# MCU.net
KiCad netlist of a schematic drawn in Altium Designer
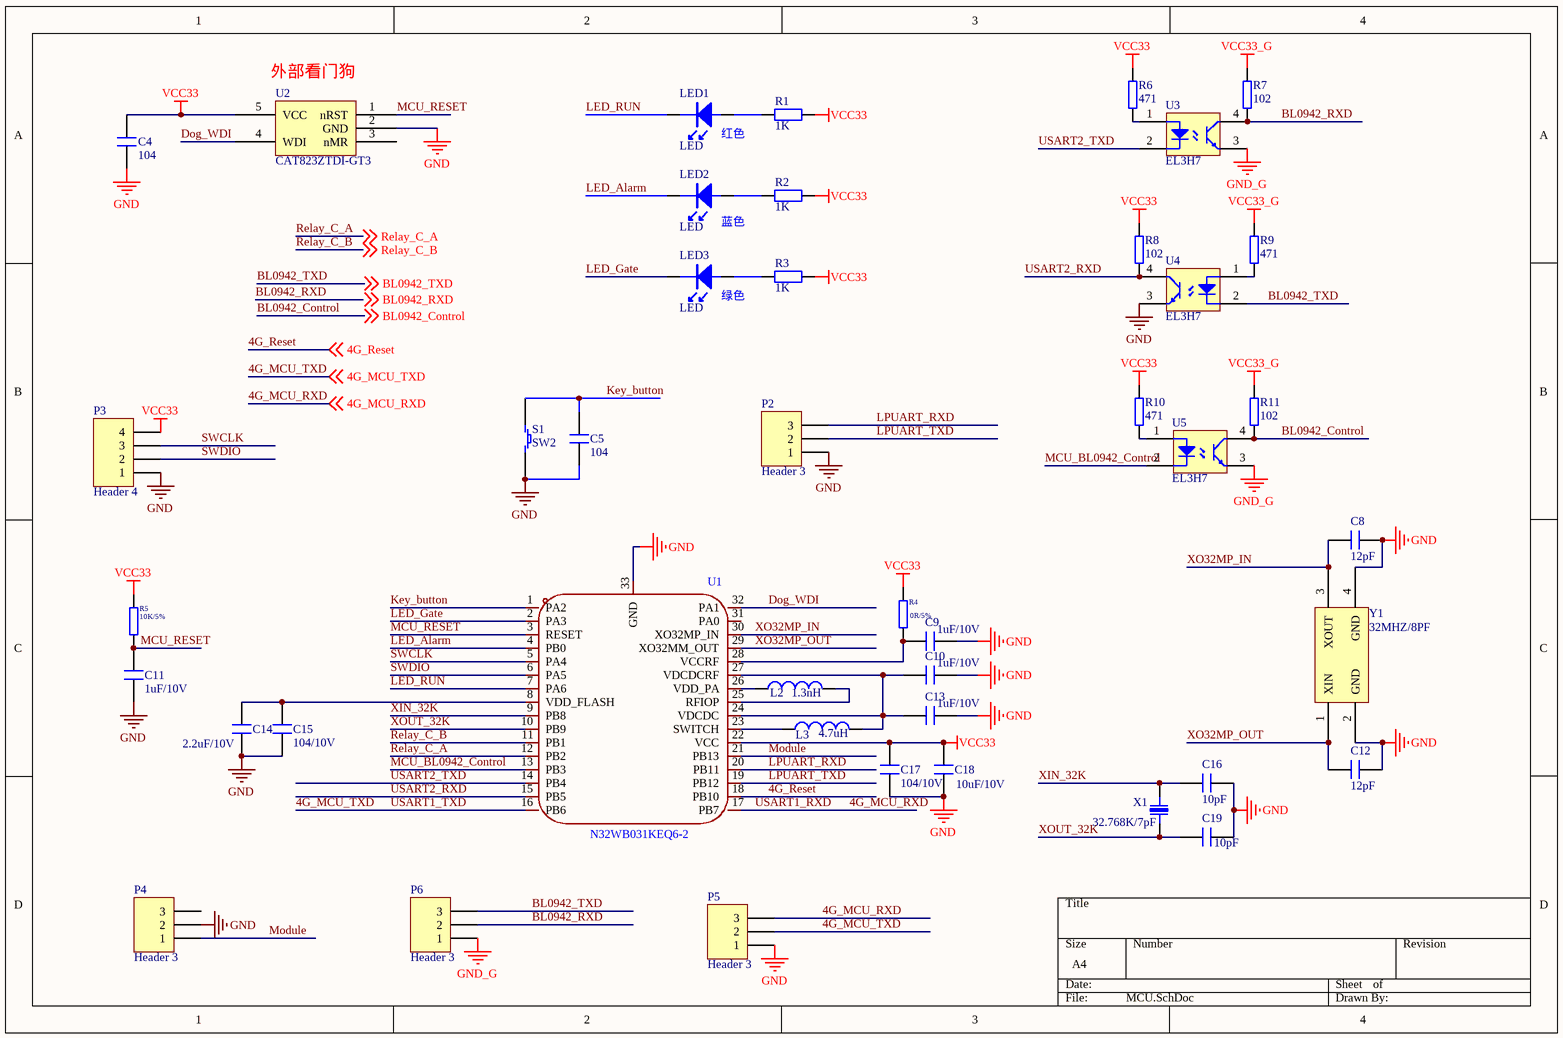
[diagram p0: MCU.SchDoc]

(export (version "E")
  (design (tool "Eeschema 10.0.6"))
  (components
    (comp (ref "C4") (value "104") (footprint "0603R") (libsource (lib "ES_Schematic") (part "CAP")))
    (comp (ref "C5") (value "104") (footprint "0603R") (libsource (lib "ES_Schematic") (part "CAP")))
    (comp (ref "C8") (value "12pF") (footprint "0603r") (libsource (lib "ES_Schematic") (part "CAP")))
    (comp (ref "C9") (value "1uF/10V") (footprint "0603R") (libsource (lib "ES_Schematic") (part "CAP_1")))
    (comp (ref "C10") (value "1uF/10V") (footprint "0603R") (libsource (lib "ES_Schematic") (part "CAP_1")))
    (comp (ref "C11") (value "1uF/10V") (footprint "0603R") (libsource (lib "ES_Schematic") (part "CAP_1")))
    (comp (ref "C12") (value "12pF") (footprint "0603r") (libsource (lib "ES_Schematic") (part "CAP")))
    (comp (ref "C13") (value "1uF/10V") (footprint "0603R") (libsource (lib "ES_Schematic") (part "CAP_1")))
    (comp (ref "C14") (value "2.2uF/10V") (footprint "0603R") (libsource (lib "ES_Schematic") (part "CAP_1")))
    (comp (ref "C15") (value "104/10V") (footprint "0603R") (libsource (lib "ES_Schematic") (part "CAP_1")))
    (comp (ref "C16") (value "10pF") (footprint "0603r") (libsource (lib "ES_Schematic") (part "CAP")))
    (comp (ref "C17") (value "104/10V") (footprint "0603R") (libsource (lib "ES_Schematic") (part "CAP_1")))
    (comp (ref "C18") (value "10uF/10V") (footprint "0603R") (libsource (lib "ES_Schematic") (part "CAP_1")))
    (comp (ref "C19") (value "10pF") (footprint "0603r") (libsource (lib "ES_Schematic") (part "CAP")))
    (comp (ref "L2")
      (value "1.3nH")
      (footprint "0603R")
      (description "Inductor")
      (fields (field (name "PUBLISHER") "Altium Limited"))
      (libsource (lib "Miscellaneous Devices") (part "Inductor"))
    )
    (comp (ref "L3")
      (value "4.7uH")
      (footprint "0603R")
      (description "Inductor")
      (fields (field (name "PUBLISHER") "Altium Limited"))
      (libsource (lib "Miscellaneous Devices") (part "Inductor"))
    )
    (comp (ref "LED1") (value "LED") (footprint "LED0805") (libsource (lib "ES_Schematic") (part "LED")))
    (comp (ref "LED2") (value "LED") (footprint "LED0805") (libsource (lib "ES_Schematic") (part "LED")))
    (comp (ref "LED3") (value "LED") (footprint "LED0805") (libsource (lib "ES_Schematic") (part "LED")))
    (comp (ref "P2")
      (value "Header 3")
      (footprint "HDR1X3")
      (description "Header, 3-Pin")
      (fields (field (name "PUBLISHER") "Altium Limited"))
      (libsource (lib "Miscellaneous Connectors") (part "Header 3"))
    )
    (comp (ref "P3")
      (value "Header 4")
      (footprint "HDR1X4")
      (description "Header, 4-Pin")
      (fields (field (name "PUBLISHER") "Altium Limited"))
      (libsource (lib "Miscellaneous Connectors") (part "Header 4"))
    )
    (comp (ref "P4")
      (value "Header 3")
      (footprint "Ss-12D00")
      (description "Header, 3-Pin")
      (fields (field (name "PUBLISHER") "Altium Limited"))
      (libsource (lib "Miscellaneous Connectors") (part "Header 3"))
    )
    (comp (ref "P5")
      (value "Header 3")
      (footprint "HDR1X3")
      (description "Header, 3-Pin")
      (fields (field (name "PUBLISHER") "Altium Limited"))
      (libsource (lib "Miscellaneous Connectors") (part "Header 3"))
    )
    (comp (ref "P6")
      (value "Header 3")
      (footprint "HDR1X3")
      (description "Header, 3-Pin")
      (fields (field (name "PUBLISHER") "Altium Limited"))
      (libsource (lib "Miscellaneous Connectors") (part "Header 3"))
    )
    (comp (ref "R1")
      (value "1K")
      (footprint "0603R")
      (fields (field (name "Comment") "Res2") (field (name "PUBLISHER") "Altium Limited"))
      (libsource (lib "Miscellaneous Devices") (part "Res2"))
    )
    (comp (ref "R2")
      (value "1K")
      (footprint "0603R")
      (fields (field (name "Comment") "Res2") (field (name "PUBLISHER") "Altium Limited"))
      (libsource (lib "Miscellaneous Devices") (part "Res2"))
    )
    (comp (ref "R3")
      (value "1K")
      (footprint "0603R")
      (fields (field (name "Comment") "Res2") (field (name "PUBLISHER") "Altium Limited"))
      (libsource (lib "Miscellaneous Devices") (part "Res2"))
    )
    (comp (ref "R4") (value "0R/5%") (footprint "0603R") (libsource (lib "ES_Schematic") (part "RES")))
    (comp (ref "R5") (value "10K/5%") (footprint "0603R") (libsource (lib "ES_Schematic") (part "RES")))
    (comp (ref "R6") (value "471") (footprint "0603R") (libsource (lib "ES_Schematic") (part "RES")))
    (comp (ref "R7") (value "102") (footprint "0603R") (libsource (lib "ES_Schematic") (part "RES")))
    (comp (ref "R8") (value "102") (footprint "0603R") (libsource (lib "ES_Schematic") (part "RES")))
    (comp (ref "R9") (value "471") (footprint "0603R") (libsource (lib "ES_Schematic") (part "RES")))
    (comp (ref "R10") (value "471") (footprint "0603R") (libsource (lib "ES_Schematic") (part "RES")))
    (comp (ref "R11") (value "102") (footprint "0603R") (libsource (lib "ES_Schematic") (part "RES")))
    (comp (ref "S1")
      (value "SW2")
      (footprint "4.5*4.5贴片4脚独立按键")
      (libsource (lib "ES_Schematic") (part "SW2"))
    )
    (comp (ref "U1")
      (value "N32WB031KEQ6-2")
      (footprint "QFN-32_L4.0-W4.0-P0.40-TL-EP2.8")
      (fields (field (name "MANUFACTURER") "Nations(国民技术)"))
      (libsource (lib "altium-import") (part "root_0_N32WB031KEQ6-2_"))
    )
    (comp (ref "U2")
      (value "CAT823ZTDI-GT3")
      (footprint "SOT-23-5")
      (libsource (lib "ES_Schematic") (part "CAT823"))
    )
    (comp (ref "U3") (value "EL3H7") (footprint "EL3H7") (libsource (lib "") (part "Optical_Coupler_1_1")))
    (comp (ref "U4")
      (value "EL3H7")
      (footprint "EL3H7")
      (libsource (lib "ES_Schematic") (part "Optical_Coupler_1"))
    )
    (comp (ref "U5") (value "EL3H7") (footprint "EL3H7") (libsource (lib "") (part "Optical_Coupler_1_1")))
    (comp (ref "X1") (value "32.768K/7pF") (footprint "Y3215") (libsource (lib "ES_Schematic") (part "XTAL")))
    (comp (ref "Y1") (value "32MHZ/8PF") (footprint "3225") (libsource (lib "others") (part "12MHz无源")))
  )
  (nets
    (net (code "1") (name "/Dog_WDI") (class "Default")
      (node (ref "U1") (pin "32") (pinfunction "PA1_32") (pintype "passive"))
      (node (ref "U2") (pin "4") (pinfunction "WDI_4") (pintype "passive"))
    )
    (net (code "2") (name "/Key_button") (class "Default")
      (node (ref "C5") (pin "1") (pinfunction "1_1") (pintype "passive"))
      (node (ref "S1") (pin "1") (pinfunction "1_1") (pintype "passive"))
      (node (ref "U1") (pin "1") (pinfunction "PA2_1") (pintype "passive"))
    )
    (net (code "3") (name "/LED_Alarm") (class "Default")
      (node (ref "LED2") (pin "2") (pinfunction "2_2") (pintype "passive"))
      (node (ref "U1") (pin "4") (pinfunction "PB0_4") (pintype "passive"))
    )
    (net (code "4") (name "/LED_Gate") (class "Default")
      (node (ref "LED3") (pin "2") (pinfunction "2_2") (pintype "passive"))
      (node (ref "U1") (pin "2") (pinfunction "PA3_2") (pintype "passive"))
    )
    (net (code "5") (name "/LED_RUN") (class "Default")
      (node (ref "LED1") (pin "2") (pinfunction "2_2") (pintype "passive"))
      (node (ref "U1") (pin "7") (pinfunction "PA6_7") (pintype "passive"))
    )
    (net (code "6") (name "/LPUART_RXD") (class "Default")
      (node (ref "P2") (pin "3") (pinfunction "3_3") (pintype "passive"))
      (node (ref "U1") (pin "20") (pinfunction "PB11_20") (pintype "passive"))
    )
    (net (code "7") (name "/LPUART_TXD") (class "Default")
      (node (ref "P2") (pin "2") (pinfunction "2_2") (pintype "passive"))
      (node (ref "U1") (pin "19") (pinfunction "PB12_19") (pintype "passive"))
    )
    (net (code "8") (name "/MCU_BL0942_Control") (class "Default")
      (node (ref "U1") (pin "13") (pinfunction "PB3_13") (pintype "passive"))
      (node (ref "U5") (pin "2") (pinfunction "K_2") (pintype "passive"))
    )
    (net (code "9") (name "/MCU_RESET") (class "Default")
      (node (ref "C11") (pin "2") (pinfunction "2_2") (pintype "passive"))
      (node (ref "R5") (pin "2") (pinfunction "2_2") (pintype "passive"))
      (node (ref "U1") (pin "3") (pinfunction "RESET_3") (pintype "passive"))
      (node (ref "U2") (pin "1") (pinfunction "nRST_1") (pintype "passive"))
    )
    (net (code "10") (name "/Module") (class "Default")
      (node (ref "P4") (pin "1") (pinfunction "1_1") (pintype "passive"))
      (node (ref "U1") (pin "21") (pinfunction "PB13_21") (pintype "passive"))
    )
    (net (code "11") (name "/SWCLK") (class "Default")
      (node (ref "P3") (pin "3") (pinfunction "3_3") (pintype "passive"))
      (node (ref "U1") (pin "5") (pinfunction "PA4_5") (pintype "passive"))
    )
    (net (code "12") (name "/SWDIO") (class "Default")
      (node (ref "P3") (pin "2") (pinfunction "2_2") (pintype "passive"))
      (node (ref "U1") (pin "6") (pinfunction "PA5_6") (pintype "passive"))
    )
    (net (code "13") (name "/USART2_RXD") (class "Default")
      (node (ref "R8") (pin "1") (pinfunction "1_1") (pintype "passive"))
      (node (ref "U1") (pin "15") (pinfunction "PB5_15") (pintype "passive"))
      (node (ref "U4") (pin "4") (pinfunction "C_4") (pintype "passive"))
    )
    (net (code "14") (name "/USART2_TXD") (class "Default")
      (node (ref "U1") (pin "14") (pinfunction "PB4_14") (pintype "passive"))
      (node (ref "U3") (pin "2") (pinfunction "K_2") (pintype "passive"))
    )
    (net (code "15") (name "/XIN_32K") (class "Default")
      (node (ref "C16") (pin "1") (pinfunction "1_1") (pintype "passive"))
      (node (ref "U1") (pin "9") (pinfunction "PB8_9") (pintype "passive"))
      (node (ref "X1") (pin "2") (pinfunction "2_2") (pintype "passive"))
    )
    (net (code "16") (name "/XO32MP_IN") (class "Default")
      (node (ref "C8") (pin "2") (pinfunction "2_2") (pintype "passive"))
      (node (ref "U1") (pin "30") (pinfunction "XO32MP_IN_30") (pintype "passive"))
      (node (ref "Y1") (pin "3") (pinfunction "XOUT_3") (pintype "passive"))
    )
    (net (code "17") (name "/XO32MP_OUT") (class "Default")
      (node (ref "C12") (pin "2") (pinfunction "2_2") (pintype "passive"))
      (node (ref "U1") (pin "29") (pinfunction "XO32MM_OUT_29") (pintype "passive"))
      (node (ref "Y1") (pin "1") (pinfunction "XIN_1") (pintype "passive"))
    )
    (net (code "18") (name "/XOUT_32K") (class "Default")
      (node (ref "C19") (pin "2") (pinfunction "2_2") (pintype "passive"))
      (node (ref "U1") (pin "10") (pinfunction "PB9_10") (pintype "passive"))
      (node (ref "X1") (pin "1") (pinfunction "1_1") (pintype "passive"))
    )
    (net (code "19") (name "4G_MCU_RXD") (class "Default")
      (node (ref "P5") (pin "3") (pinfunction "3_3") (pintype "passive"))
      (node (ref "U1") (pin "17") (pinfunction "PB7_17") (pintype "passive"))
    )
    (net (code "20") (name "4G_MCU_TXD") (class "Default")
      (node (ref "P5") (pin "2") (pinfunction "2_2") (pintype "passive"))
      (node (ref "U1") (pin "16") (pinfunction "PB6_16") (pintype "passive"))
    )
    (net (code "21") (name "4G_Reset") (class "Default")
      (node (ref "U1") (pin "18") (pinfunction "PB10_18") (pintype "passive"))
    )
    (net (code "22") (name "BL0942_Control") (class "Default")
      (node (ref "R11") (pin "1") (pinfunction "1_1") (pintype "passive"))
      (node (ref "U5") (pin "4") (pinfunction "C_4") (pintype "passive"))
    )
    (net (code "23") (name "BL0942_RXD") (class "Default")
      (node (ref "P6") (pin "2") (pinfunction "2_2") (pintype "passive"))
      (node (ref "R7") (pin "1") (pinfunction "1_1") (pintype "passive"))
      (node (ref "U3") (pin "4") (pinfunction "C_4") (pintype "passive"))
    )
    (net (code "24") (name "BL0942_TXD") (class "Default")
      (node (ref "P6") (pin "3") (pinfunction "3_3") (pintype "passive"))
      (node (ref "U4") (pin "2") (pinfunction "K_2") (pintype "passive"))
    )
    (net (code "25") (name "GND") (class "Default")
      (node (ref "C10") (pin "1") (pinfunction "1_1") (pintype "passive"))
      (node (ref "C11") (pin "1") (pinfunction "1_1") (pintype "passive"))
      (node (ref "C12") (pin "1") (pinfunction "1_1") (pintype "passive"))
      (node (ref "C13") (pin "1") (pinfunction "1_1") (pintype "passive"))
      (node (ref "C14") (pin "1") (pinfunction "1_1") (pintype "passive"))
      (node (ref "C15") (pin "1") (pinfunction "1_1") (pintype "passive"))
      (node (ref "C16") (pin "2") (pinfunction "2_2") (pintype "passive"))
      (node (ref "C17") (pin "1") (pinfunction "1_1") (pintype "passive"))
      (node (ref "C18") (pin "1") (pinfunction "1_1") (pintype "passive"))
      (node (ref "C19") (pin "1") (pinfunction "1_1") (pintype "passive"))
      (node (ref "C4") (pin "1") (pinfunction "1_1") (pintype "passive"))
      (node (ref "C5") (pin "2") (pinfunction "2_2") (pintype "passive"))
      (node (ref "C8") (pin "1") (pinfunction "1_1") (pintype "passive"))
      (node (ref "C9") (pin "1") (pinfunction "1_1") (pintype "passive"))
      (node (ref "P2") (pin "1") (pinfunction "1_1") (pintype "passive"))
      (node (ref "P3") (pin "1") (pinfunction "1_1") (pintype "passive"))
      (node (ref "P4") (pin "2") (pinfunction "2_2") (pintype "passive"))
      (node (ref "P5") (pin "1") (pinfunction "1_1") (pintype "passive"))
      (node (ref "S1") (pin "2") (pinfunction "2_2") (pintype "passive"))
      (node (ref "U1") (pin "33") (pinfunction "GND_33") (pintype "passive"))
      (node (ref "U2") (pin "2") (pinfunction "GND_2") (pintype "passive"))
      (node (ref "U4") (pin "3") (pinfunction "E_3") (pintype "passive"))
      (node (ref "Y1") (pin "2") (pinfunction "GND_2") (pintype "passive"))
      (node (ref "Y1") (pin "4") (pinfunction "GND_4") (pintype "passive"))
    )
    (net (code "26") (name "GND_G") (class "Default")
      (node (ref "P6") (pin "1") (pinfunction "1_1") (pintype "passive"))
      (node (ref "U3") (pin "3") (pinfunction "E_3") (pintype "passive"))
      (node (ref "U5") (pin "3") (pinfunction "E_3") (pintype "passive"))
    )
    (net (code "27") (name "Net-(LED1-Pad1)") (class "Default")
      (node (ref "LED1") (pin "1") (pinfunction "1_1") (pintype "passive"))
      (node (ref "R1") (pin "2") (pinfunction "2_2") (pintype "passive"))
    )
    (net (code "28") (name "Net-(LED2-Pad1)") (class "Default")
      (node (ref "LED2") (pin "1") (pinfunction "1_1") (pintype "passive"))
      (node (ref "R2") (pin "2") (pinfunction "2_2") (pintype "passive"))
    )
    (net (code "29") (name "Net-(LED3-Pad1)") (class "Default")
      (node (ref "LED3") (pin "1") (pinfunction "1_1") (pintype "passive"))
      (node (ref "R3") (pin "2") (pinfunction "2_2") (pintype "passive"))
    )
    (net (code "30") (name "Net-(U1-RFIOP)") (class "Default")
      (node (ref "L2") (pin "2") (pinfunction "2_2") (pintype "passive"))
      (node (ref "U1") (pin "25") (pinfunction "RFIOP_25") (pintype "passive"))
    )
    (net (code "31") (name "Net-(U1-SWITCH)") (class "Default")
      (node (ref "L3") (pin "1") (pinfunction "1_1") (pintype "passive"))
      (node (ref "U1") (pin "23") (pinfunction "SWITCH_23") (pintype "passive"))
    )
    (net (code "32") (name "Net-(U1-VCCRF)") (class "Default")
      (node (ref "C9") (pin "2") (pinfunction "2_2") (pintype "passive"))
      (node (ref "R4") (pin "2") (pinfunction "2_2") (pintype "passive"))
      (node (ref "U1") (pin "28") (pinfunction "VCCRF_28") (pintype "passive"))
    )
    (net (code "33") (name "Net-(U1-VDCDC)") (class "Default")
      (node (ref "C10") (pin "2") (pinfunction "2_2") (pintype "passive"))
      (node (ref "C13") (pin "2") (pinfunction "2_2") (pintype "passive"))
      (node (ref "L3") (pin "2") (pinfunction "2_2") (pintype "passive"))
      (node (ref "U1") (pin "24") (pinfunction "VDCDC_24") (pintype "passive"))
      (node (ref "U1") (pin "27") (pinfunction "VDCDCRF_27") (pintype "passive"))
    )
    (net (code "34") (name "Net-(U1-VDD_FLASH)") (class "Default")
      (node (ref "C14") (pin "2") (pinfunction "2_2") (pintype "passive"))
      (node (ref "C15") (pin "2") (pinfunction "2_2") (pintype "passive"))
      (node (ref "U1") (pin "8") (pinfunction "VDD_FLASH_8") (pintype "passive"))
    )
    (net (code "35") (name "Net-(U1-VDD_PA)") (class "Default")
      (node (ref "L2") (pin "1") (pinfunction "1_1") (pintype "passive"))
      (node (ref "U1") (pin "26") (pinfunction "VDD_PA_26") (pintype "passive"))
    )
    (net (code "36") (name "Net-(U3-A)") (class "Default")
      (node (ref "R6") (pin "2") (pinfunction "2_2") (pintype "passive"))
      (node (ref "U3") (pin "1") (pinfunction "A_1") (pintype "passive"))
    )
    (net (code "37") (name "Net-(U4-A)") (class "Default")
      (node (ref "R9") (pin "2") (pinfunction "2_2") (pintype "passive"))
      (node (ref "U4") (pin "1") (pinfunction "A_1") (pintype "passive"))
    )
    (net (code "38") (name "Net-(U5-A)") (class "Default")
      (node (ref "R10") (pin "2") (pinfunction "2_2") (pintype "passive"))
      (node (ref "U5") (pin "1") (pinfunction "A_1") (pintype "passive"))
    )
    (net (code "39") (name "Relay_C_A") (class "Default")
      (node (ref "U1") (pin "12") (pinfunction "PB2_12") (pintype "passive"))
    )
    (net (code "40") (name "Relay_C_B") (class "Default")
      (node (ref "U1") (pin "11") (pinfunction "PB1_11") (pintype "passive"))
    )
    (net (code "41") (name "VCC33") (class "Default")
      (node (ref "C17") (pin "2") (pinfunction "2_2") (pintype "passive"))
      (node (ref "C18") (pin "2") (pinfunction "2_2") (pintype "passive"))
      (node (ref "C4") (pin "2") (pinfunction "2_2") (pintype "passive"))
      (node (ref "P3") (pin "4") (pinfunction "4_4") (pintype "passive"))
      (node (ref "R1") (pin "1") (pinfunction "1_1") (pintype "passive"))
      (node (ref "R10") (pin "1") (pinfunction "1_1") (pintype "passive"))
      (node (ref "R2") (pin "1") (pinfunction "1_1") (pintype "passive"))
      (node (ref "R3") (pin "1") (pinfunction "1_1") (pintype "passive"))
      (node (ref "R4") (pin "1") (pinfunction "1_1") (pintype "passive"))
      (node (ref "R5") (pin "1") (pinfunction "1_1") (pintype "passive"))
      (node (ref "R6") (pin "1") (pinfunction "1_1") (pintype "passive"))
      (node (ref "R8") (pin "2") (pinfunction "2_2") (pintype "passive"))
      (node (ref "U1") (pin "22") (pinfunction "VCC_22") (pintype "passive"))
      (node (ref "U2") (pin "5") (pinfunction "VCC_5") (pintype "passive"))
    )
    (net (code "42") (name "VCC33_G") (class "Default")
      (node (ref "R11") (pin "2") (pinfunction "2_2") (pintype "passive"))
      (node (ref "R7") (pin "2") (pinfunction "2_2") (pintype "passive"))
      (node (ref "R9") (pin "1") (pinfunction "1_1") (pintype "passive"))
    )
    (net (code "43") (name "unconnected-(P4-Pad3)") (class "Default")
      (node (ref "P4") (pin "3") (pinfunction "3_3") (pintype "passive"))
    )
    (net (code "44") (name "unconnected-(U1-PA0-Pad31)") (class "Default")
      (node (ref "U1") (pin "31") (pinfunction "PA0_31") (pintype "passive"))
    )
    (net (code "45") (name "unconnected-(U2-nMR-Pad3)") (class "Default")
      (node (ref "U2") (pin "3") (pinfunction "nMR_3") (pintype "passive"))
    )
  )
)
